# management-i2c.net
KiCad netlist of a schematic drawn in Altium Designer
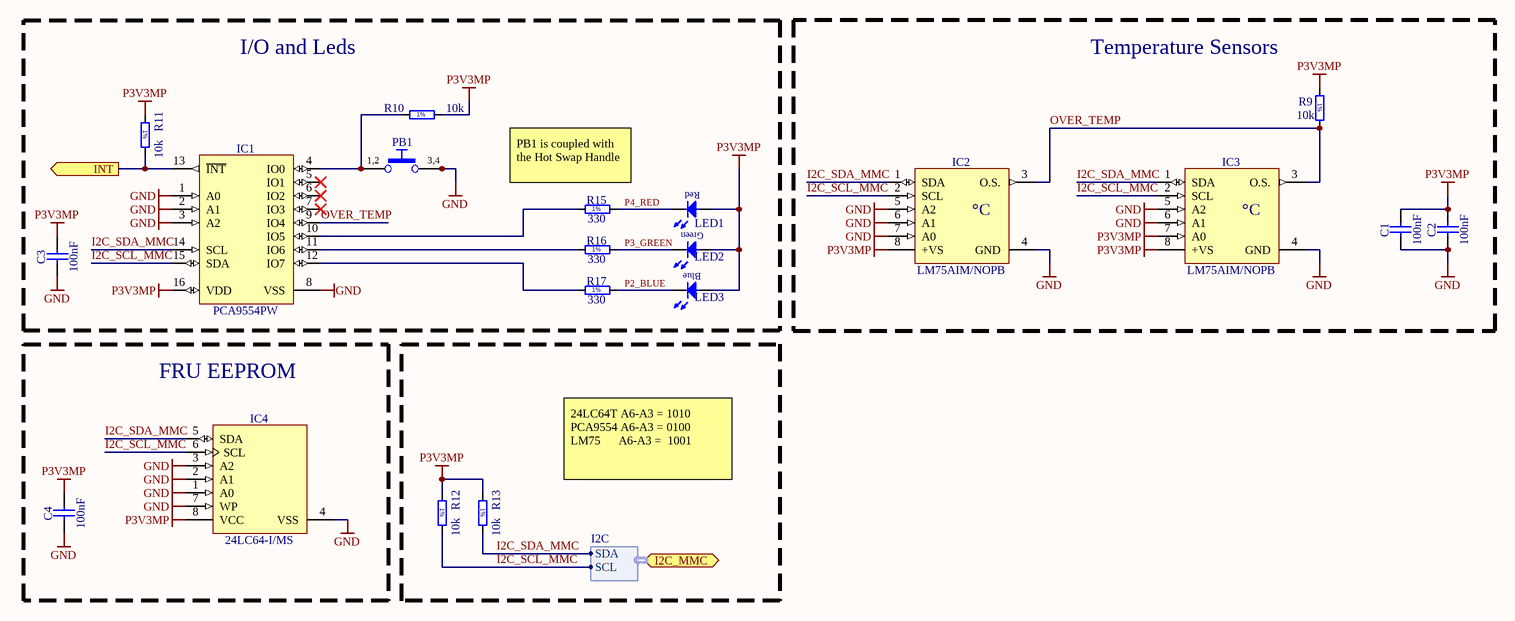
[diagram p0: management-i2c.SchDoc]

(export (version "E")
  (design (tool "Eeschema 10.0.6"))
  (components
    (comp (ref "C1")
      (value "100nF")
      (footprint "CAPC1005X55N")
      (description "Non-polarised capacitor")
      (fields
        (field (name "PART NUMBER") "CC0402_100NF_16V_10%_X7R")
        (field (name "VOLTAGE") "16V")
        (field (name "AUTHOR") "CERN DEM JLC")
      )
      (libsource (lib "Capacitors") (part "Capacitor - non polarized"))
    )
    (comp (ref "C2")
      (value "100nF")
      (footprint "CAPC1005X55N")
      (description "Non-polarised capacitor")
      (fields
        (field (name "PART NUMBER") "CC0402_100NF_16V_10%_X7R")
        (field (name "VOLTAGE") "16V")
        (field (name "AUTHOR") "CERN DEM JLC")
      )
      (libsource (lib "Capacitors") (part "Capacitor - non polarized"))
    )
    (comp (ref "C3")
      (value "100nF")
      (footprint "CAPC1005X55N")
      (description "Non-polarised capacitor")
      (fields
        (field (name "PART NUMBER") "CC0402_100NF_16V_10%_X7R")
        (field (name "VOLTAGE") "16V")
        (field (name "AUTHOR") "CERN DEM JLC")
      )
      (libsource (lib "Capacitors") (part "Capacitor - non polarized"))
    )
    (comp (ref "C4")
      (value "100nF")
      (footprint "CAPC1005X55N")
      (description "Non-polarised capacitor")
      (fields
        (field (name "PART NUMBER") "CC0402_100NF_16V_10%_X7R")
        (field (name "VOLTAGE") "16V")
        (field (name "AUTHOR") "CERN DEM JLC")
      )
      (libsource (lib "Capacitors") (part "Capacitor - non polarized"))
    )
    (comp (ref "IC1")
      (value "PCA9554PW")
      (footprint "SOP65P640X110-16N")
      (description "8-Bit I2C-Bus and SMBus I/O Port with Interrupt")
      (fields (field (name "MANUFACTURER") "NXP SEMICONDUCTORS") (field (name "AUTHOR") "CERN DEM JLC"))
      (libsource (lib "ICs And Semiconductors") (part "PCA9554PW"))
    )
    (comp (ref "IC2")
      (value "LM75AIM/NOPB")
      (footprint "SOIC127P600X175-8N")
      (description "Digital Temperature Sensor and Thermal Watchdog with Two-Wire Interface")
      (fields (field (name "MANUFACTURER") "TEXAS INSTRUMENTS") (field (name "AUTHOR") "CERN DEM JLC"))
      (libsource (lib "ICs And Semiconductors") (part "LM75"))
    )
    (comp (ref "IC3")
      (value "LM75AIM/NOPB")
      (footprint "SOIC127P600X175-8N")
      (description "Digital Temperature Sensor and Thermal Watchdog with Two-Wire Interface")
      (fields (field (name "MANUFACTURER") "TEXAS INSTRUMENTS") (field (name "AUTHOR") "CERN DEM JLC"))
      (libsource (lib "ICs And Semiconductors") (part "LM75"))
    )
    (comp (ref "IC4")
      (value "24LC64-I/MS")
      (footprint "SOP65P490X110-8N")
      (description "64K I2C Serial EEPROM")
      (fields (field (name "MANUFACTURER") "MICROCHIP TECHNOLOGY") (field (name "AUTHOR") "CERN DEM JLC"))
      (libsource (lib "ICs And Semiconductors") (part "24LC64-I/MS"))
    )
    (comp (ref "LED1")
      (value "Red")
      (footprint "LEDC1608X80N_RED")
      (description "LED Red 1C 2A")
      (fields
        (field (name "PART NUMBER") "LED_ROHM_SML-311UTT86K")
        (field (name "MANUFACTURER") "ROHM")
        (field (name "AUTHOR") "CERN DEM JLC")
      )
      (libsource (lib "ICs And Semiconductors") (part "LED Red 1C 2A"))
    )
    (comp (ref "LED2")
      (value "Green")
      (footprint "LED_AVAGO_HSME-C120")
      (description "LED Green 1C 2A")
      (fields
        (field (name "PART NUMBER") "LED_AVAGO_HSME-C120")
        (field (name "MANUFACTURER") "AVAGO TECHNOLOGIES")
        (field (name "AUTHOR") "CERN DEM JMW")
      )
      (libsource (lib "ICs And Semiconductors") (part "LED Green 1C 2A"))
    )
    (comp (ref "LED3")
      (value "Blue")
      (footprint "LED_AVAGO_HSMR-C120")
      (description "LED Blue 1C 2A")
      (fields
        (field (name "PART NUMBER") "LED_AVAGO_HSMR-C120")
        (field (name "MANUFACTURER") "AVAGO TECHNOLOGIES")
        (field (name "AUTHOR") "CERN DEM JLC")
      )
      (libsource (lib "ICs And Semiconductors") (part "LED Blue 1C 2A"))
    )
    (comp (ref "PB1")
      (value "Push Button")
      (footprint "SW_C&K_HDT0001")
      (description "Push-Button Switch SPDT")
      (fields
        (field (name "PART NUMBER") "SW_C&K_HDT0001")
        (field (name "MANUFACTURER") "C&K")
        (field (name "AUTHOR") "CERN DEM JLC")
      )
      (libsource (lib "Eletro-mechanical") (part "PB SPST 12NO-34NO"))
    )
    (comp (ref "R9")
      (value "10k")
      (footprint "RESC1005X40N")
      (description "Resistor - 1%")
      (fields
        (field (name "PART NUMBER") "R0402_10K_1%_0.0625W_100PPM")
        (field (name "POWER") "0.0625W")
        (field (name "AUTHOR") "CERN DEM JLC")
      )
      (libsource (lib "Resistors") (part "Resistor - 1%"))
    )
    (comp (ref "R10")
      (value "10k")
      (footprint "RESC1005X40N")
      (description "Resistor - 1%")
      (fields
        (field (name "PART NUMBER") "R0402_10K_1%_0.0625W_100PPM")
        (field (name "POWER") "0.0625W")
        (field (name "AUTHOR") "CERN DEM JLC")
      )
      (libsource (lib "Resistors") (part "Resistor - 1%"))
    )
    (comp (ref "R11")
      (value "10k")
      (footprint "RESC1005X40N")
      (description "Resistor - 1%")
      (fields
        (field (name "PART NUMBER") "R0402_10K_1%_0.0625W_100PPM")
        (field (name "POWER") "0.0625W")
        (field (name "AUTHOR") "CERN DEM JLC")
      )
      (libsource (lib "Resistors") (part "Resistor - 1%"))
    )
    (comp (ref "R12")
      (value "10k")
      (footprint "RESC1005X40N")
      (description "Resistor - 1%")
      (fields
        (field (name "PART NUMBER") "R0402_10K_1%_0.0625W_100PPM")
        (field (name "POWER") "0.0625W")
        (field (name "AUTHOR") "CERN DEM JLC")
      )
      (libsource (lib "Resistors") (part "Resistor - 1%"))
    )
    (comp (ref "R13")
      (value "10k")
      (footprint "RESC1005X40N")
      (description "Resistor - 1%")
      (fields
        (field (name "PART NUMBER") "R0402_10K_1%_0.0625W_100PPM")
        (field (name "POWER") "0.0625W")
        (field (name "AUTHOR") "CERN DEM JLC")
      )
      (libsource (lib "Resistors") (part "Resistor - 1%"))
    )
    (comp (ref "R15")
      (value "330")
      (footprint "RESC1608X55N")
      (description "Resistor - 1%")
      (fields
        (field (name "PART NUMBER") "R0603_330R_1%_0.1W_100PPM")
        (field (name "POWER") "0.1W")
        (field (name "AUTHOR") "CERN DEM JLC")
      )
      (libsource (lib "Resistors") (part "Resistor - 1%"))
    )
    (comp (ref "R16")
      (value "330")
      (footprint "RESC1608X55N")
      (description "Resistor - 1%")
      (fields
        (field (name "PART NUMBER") "R0603_330R_1%_0.1W_100PPM")
        (field (name "POWER") "0.1W")
        (field (name "AUTHOR") "CERN DEM JLC")
      )
      (libsource (lib "Resistors") (part "Resistor - 1%"))
    )
    (comp (ref "R17")
      (value "330")
      (footprint "RESC1608X55N")
      (description "Resistor - 1%")
      (fields
        (field (name "PART NUMBER") "R0603_330R_1%_0.1W_100PPM")
        (field (name "POWER") "0.1W")
        (field (name "AUTHOR") "CERN DEM JLC")
      )
      (libsource (lib "Resistors") (part "Resistor - 1%"))
    )
  )
  (nets
    (net (code "2") (name "/I2C_SCL_MMC") (class "Default")
      (node (ref "IC1") (pin "15") (pinfunction "SDA_15") (pintype "bidirectional"))
      (node (ref "IC2") (pin "2") (pinfunction "SCL_2") (pintype "input"))
      (node (ref "IC3") (pin "2") (pinfunction "SCL_2") (pintype "input"))
      (node (ref "IC4") (pin "6") (pinfunction "SCL_6") (pintype "input"))
      (node (ref "R12") (pin "2") (pinfunction "2_2") (pintype "passive"))
    )
    (net (code "3") (name "/I2C_SDA_MMC") (class "Default")
      (node (ref "IC1") (pin "14") (pinfunction "SCL_14") (pintype "input"))
      (node (ref "IC2") (pin "1") (pinfunction "SDA_1") (pintype "bidirectional"))
      (node (ref "IC3") (pin "1") (pinfunction "SDA_1") (pintype "bidirectional"))
      (node (ref "IC4") (pin "5") (pinfunction "SDA_5") (pintype "bidirectional"))
      (node (ref "R13") (pin "2") (pinfunction "2_2") (pintype "passive"))
    )
    (net (code "4") (name "/INT") (class "Default")
      (node (ref "IC1") (pin "13") (pinfunction "~{INT}_13") (pintype "output"))
      (node (ref "R11") (pin "2") (pinfunction "2_2") (pintype "passive"))
    )
    (net (code "5") (name "/OVER_TEMP") (class "Default")
      (node (ref "IC1") (pin "9") (pinfunction "IO4_9") (pintype "bidirectional"))
      (node (ref "IC2") (pin "3") (pinfunction "O.S._3") (pintype "output"))
      (node (ref "IC3") (pin "3") (pinfunction "O.S._3") (pintype "output"))
      (node (ref "R9") (pin "2") (pinfunction "2_2") (pintype "passive"))
    )
    (net (code "6") (name "/P2_BLUE") (class "Default")
      (node (ref "LED3") (pin "1") (pinfunction "C_1") (pintype "passive"))
      (node (ref "R17") (pin "2") (pinfunction "2_2") (pintype "passive"))
    )
    (net (code "7") (name "/P3_GREEN") (class "Default")
      (node (ref "LED2") (pin "1") (pinfunction "C_1") (pintype "passive"))
      (node (ref "R16") (pin "2") (pinfunction "2_2") (pintype "passive"))
    )
    (net (code "8") (name "/P4_RED") (class "Default")
      (node (ref "LED1") (pin "1") (pinfunction "C_1") (pintype "passive"))
      (node (ref "R15") (pin "2") (pinfunction "2_2") (pintype "passive"))
    )
    (net (code "10") (name "GND") (class "Default")
      (node (ref "C1") (pin "2") (pinfunction "2_2") (pintype "passive"))
      (node (ref "C2") (pin "2") (pinfunction "2_2") (pintype "passive"))
      (node (ref "C3") (pin "2") (pinfunction "2_2") (pintype "passive"))
      (node (ref "C4") (pin "2") (pinfunction "2_2") (pintype "passive"))
      (node (ref "IC1") (pin "1") (pinfunction "A0_1") (pintype "input"))
      (node (ref "IC1") (pin "2") (pinfunction "A1_2") (pintype "input"))
      (node (ref "IC1") (pin "3") (pinfunction "A2_3") (pintype "input"))
      (node (ref "IC1") (pin "8") (pinfunction "VSS_8") (pintype "power_in"))
      (node (ref "IC2") (pin "4") (pinfunction "GND_4") (pintype "power_in"))
      (node (ref "IC2") (pin "5") (pinfunction "A2_5") (pintype "input"))
      (node (ref "IC2") (pin "6") (pinfunction "A1_6") (pintype "input"))
      (node (ref "IC2") (pin "7") (pinfunction "A0_7") (pintype "input"))
      (node (ref "IC3") (pin "4") (pinfunction "GND_4") (pintype "power_in"))
      (node (ref "IC3") (pin "5") (pinfunction "A2_5") (pintype "input"))
      (node (ref "IC3") (pin "6") (pinfunction "A1_6") (pintype "input"))
      (node (ref "IC4") (pin "1") (pinfunction "A0_1") (pintype "input"))
      (node (ref "IC4") (pin "2") (pinfunction "A1_2") (pintype "input"))
      (node (ref "IC4") (pin "3") (pinfunction "A2_3") (pintype "input"))
      (node (ref "IC4") (pin "4") (pinfunction "VSS_4") (pintype "power_in"))
      (node (ref "IC4") (pin "7") (pinfunction "WP_7") (pintype "input"))
      (node (ref "PB1") (pin "3") (pinfunction "3_3") (pintype "passive"))
      (node (ref "PB1") (pin "4") (pinfunction "4_4") (pintype "passive"))
    )
    (net (code "11") (name "Net-(IC1-IO0)") (class "Default")
      (node (ref "IC1") (pin "4") (pinfunction "IO0_4") (pintype "bidirectional"))
      (node (ref "PB1") (pin "1") (pinfunction "1_1") (pintype "passive"))
      (node (ref "PB1") (pin "2") (pinfunction "2_2") (pintype "passive"))
      (node (ref "R10") (pin "1") (pinfunction "1_1") (pintype "passive"))
    )
    (net (code "12") (name "Net-(IC1-IO5)") (class "Default")
      (node (ref "IC1") (pin "10") (pinfunction "IO5_10") (pintype "bidirectional"))
      (node (ref "R15") (pin "1") (pinfunction "1_1") (pintype "passive"))
    )
    (net (code "13") (name "Net-(IC1-IO6)") (class "Default")
      (node (ref "IC1") (pin "11") (pinfunction "IO6_11") (pintype "bidirectional"))
      (node (ref "R16") (pin "1") (pinfunction "1_1") (pintype "passive"))
    )
    (net (code "14") (name "Net-(IC1-IO7)") (class "Default")
      (node (ref "IC1") (pin "12") (pinfunction "IO7_12") (pintype "bidirectional"))
      (node (ref "R17") (pin "1") (pinfunction "1_1") (pintype "passive"))
    )
    (net (code "15") (name "P3V3MP") (class "Default")
      (node (ref "C1") (pin "1") (pinfunction "1_1") (pintype "passive"))
      (node (ref "C2") (pin "1") (pinfunction "1_1") (pintype "passive"))
      (node (ref "C3") (pin "1") (pinfunction "1_1") (pintype "passive"))
      (node (ref "C4") (pin "1") (pinfunction "1_1") (pintype "passive"))
      (node (ref "IC1") (pin "16") (pinfunction "VDD_16") (pintype "bidirectional"))
      (node (ref "IC2") (pin "8") (pinfunction "+VS_8") (pintype "power_in"))
      (node (ref "IC3") (pin "7") (pinfunction "A0_7") (pintype "input"))
      (node (ref "IC3") (pin "8") (pinfunction "+VS_8") (pintype "power_in"))
      (node (ref "IC4") (pin "8") (pinfunction "VCC_8") (pintype "power_in"))
      (node (ref "LED1") (pin "2") (pinfunction "A_2") (pintype "passive"))
      (node (ref "LED2") (pin "2") (pinfunction "A_2") (pintype "passive"))
      (node (ref "LED3") (pin "2") (pinfunction "A_2") (pintype "passive"))
      (node (ref "R10") (pin "2") (pinfunction "2_2") (pintype "passive"))
      (node (ref "R11") (pin "1") (pinfunction "1_1") (pintype "passive"))
      (node (ref "R12") (pin "1") (pinfunction "1_1") (pintype "passive"))
      (node (ref "R13") (pin "1") (pinfunction "1_1") (pintype "passive"))
      (node (ref "R9") (pin "1") (pinfunction "1_1") (pintype "passive"))
    )
    (net (code "16") (name "unconnected-(IC1-IO1-Pad5)") (class "Default")
      (node (ref "IC1") (pin "5") (pinfunction "IO1_5") (pintype "bidirectional+no_connect"))
    )
    (net (code "17") (name "unconnected-(IC1-IO2-Pad6)") (class "Default")
      (node (ref "IC1") (pin "6") (pinfunction "IO2_6") (pintype "bidirectional+no_connect"))
    )
    (net (code "18") (name "unconnected-(IC1-IO3-Pad7)") (class "Default")
      (node (ref "IC1") (pin "7") (pinfunction "IO3_7") (pintype "bidirectional+no_connect"))
    )
  )
)
